# PRoMo_Base_DIP.net
KiCad netlist of a schematic drawn in EAGLE
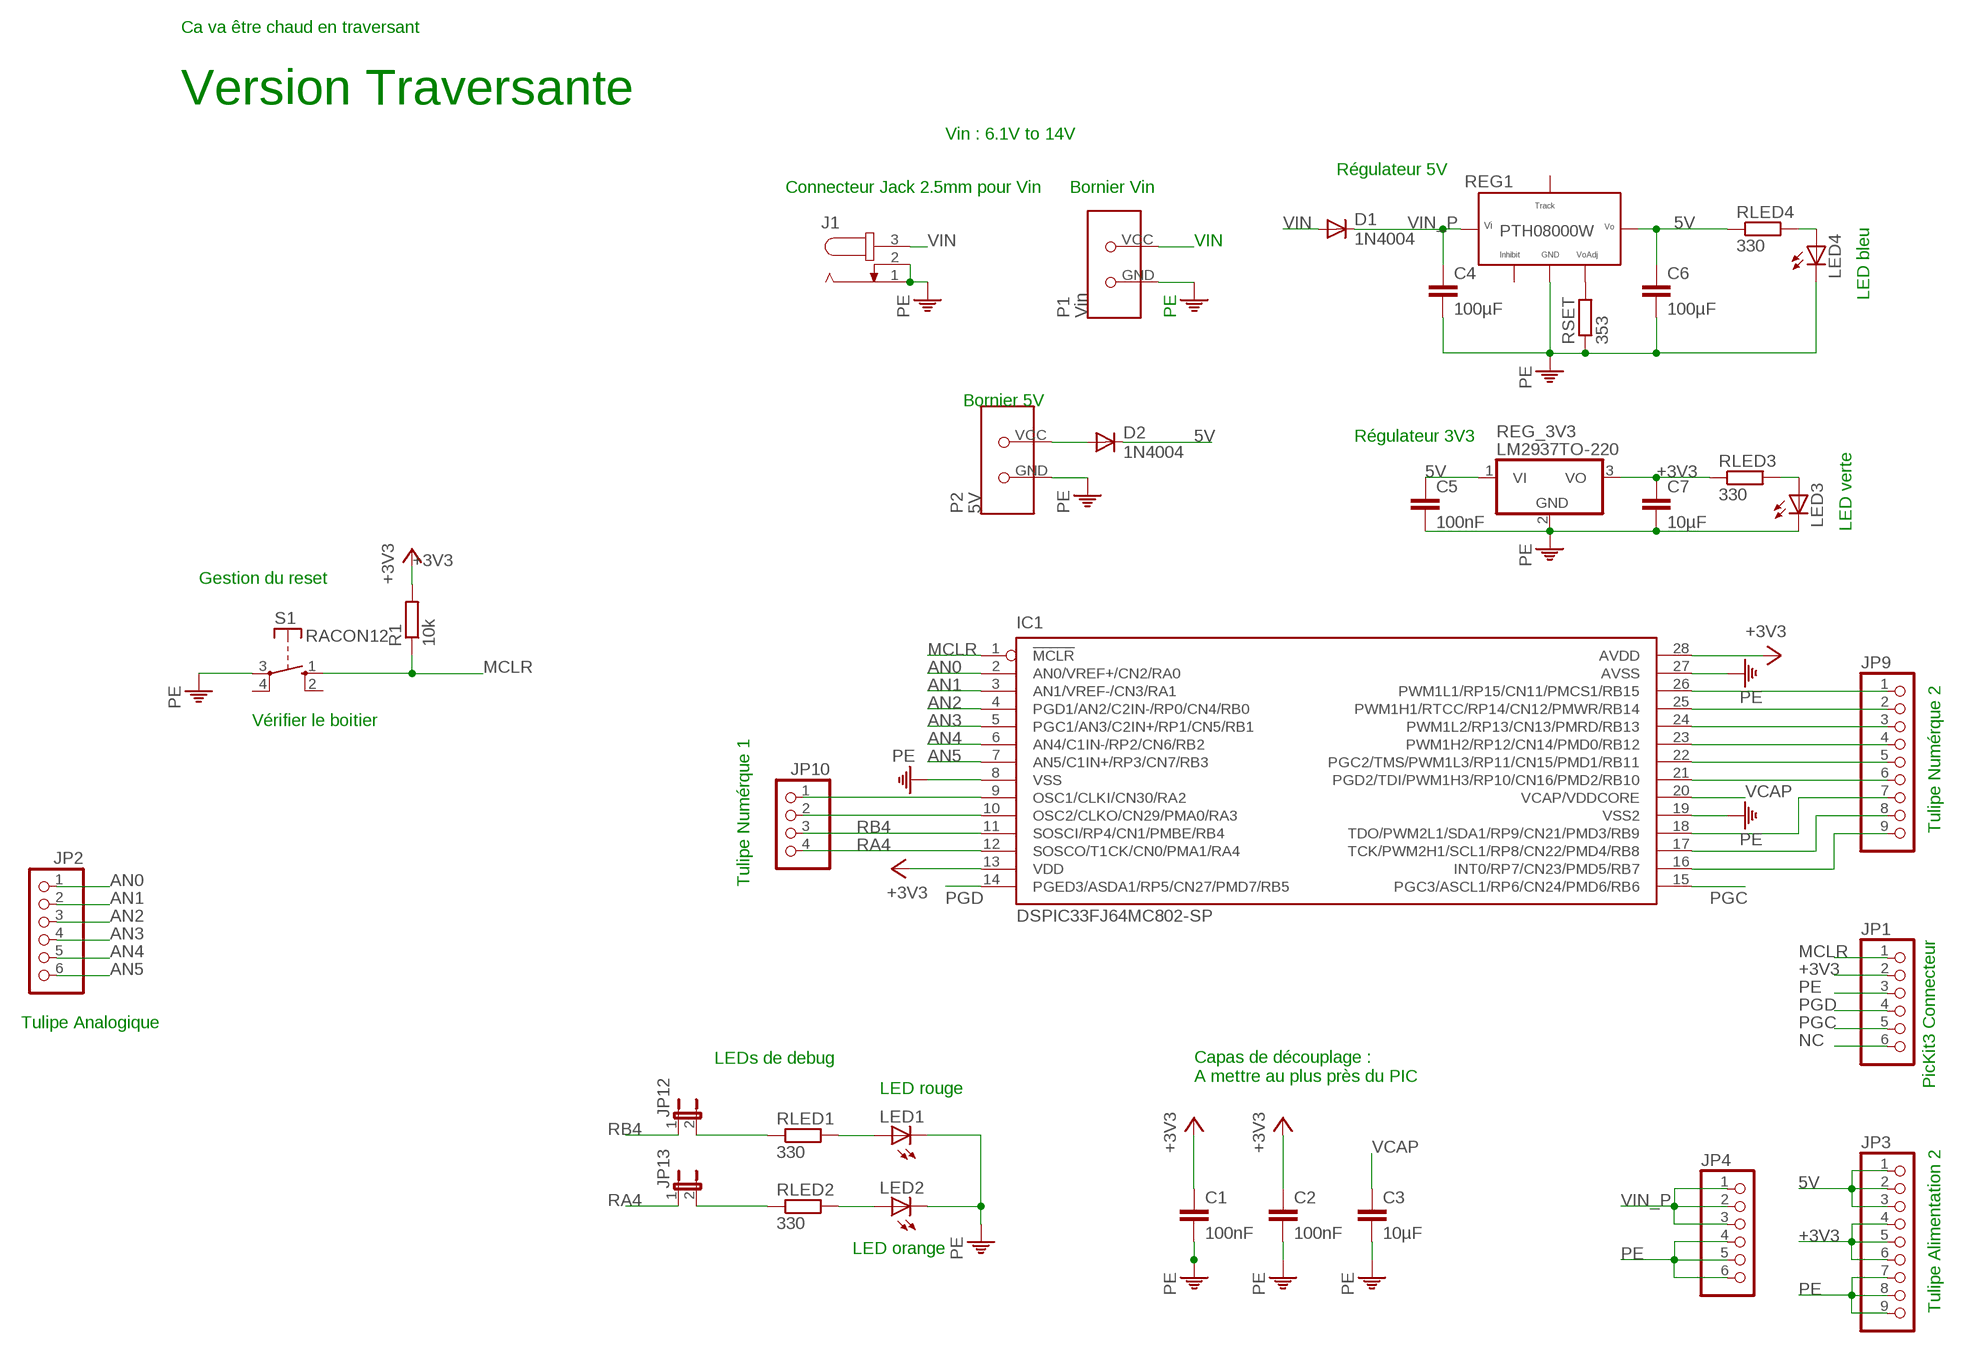
[diagram p0: schematic, sheet 1]

(export (version "E")
  (design (tool "Eeschema 10.0.6"))
  (components
    (comp (ref "C1")
      (value "100nF")
      (footprint "eagle-import:C102-043X133")
      (libsource (lib "eagle-import") (part "C-EU102-043X133"))
    )
    (comp (ref "C2")
      (value "100nF")
      (footprint "eagle-import:C050-035X075")
      (libsource (lib "eagle-import") (part "C-EU050-035X075"))
    )
    (comp (ref "C3")
      (value "10µF")
      (footprint "eagle-import:C050-035X075")
      (libsource (lib "eagle-import") (part "C-EU050-035X075"))
    )
    (comp (ref "C4")
      (value "100µF")
      (footprint "eagle-import:C050-035X075")
      (libsource (lib "eagle-import") (part "C-EU050-035X075"))
    )
    (comp (ref "C5")
      (value "100nF")
      (footprint "eagle-import:C050-035X075")
      (libsource (lib "eagle-import") (part "C-EU050-035X075"))
    )
    (comp (ref "C6")
      (value "100µF")
      (footprint "eagle-import:C050-035X075")
      (libsource (lib "eagle-import") (part "C-EU050-035X075"))
    )
    (comp (ref "C7")
      (value "10µF")
      (footprint "eagle-import:C050-035X075")
      (libsource (lib "eagle-import") (part "C-EU050-035X075"))
    )
    (comp (ref "D1")
      (value "1N4004")
      (footprint "eagle-import:DO41-10")
      (libsource (lib "eagle-import") (part "1N4004"))
    )
    (comp (ref "D2")
      (value "1N4004")
      (footprint "eagle-import:DO41-10")
      (libsource (lib "eagle-import") (part "1N4004"))
    )
    (comp (ref "IC1")
      (value "DSPIC33FJ64MC802-SP")
      (footprint "eagle-import:DIL28-3")
      (libsource (lib "eagle-import") (part "DSPIC33FJ64MC802-SP"))
    )
    (comp (ref "J1")
      (value "JACK-PLUG1")
      (footprint "eagle-import:SPC4078")
      (libsource (lib "eagle-import") (part "JACK-PLUG1"))
    )
    (comp (ref "JP1")
      (value "PINHD-1X6/90")
      (footprint "eagle-import:1X06_90")
      (libsource (lib "eagle-import") (part "PINHD-1X6/90"))
    )
    (comp (ref "JP2")
      (value "PINHD-1X6")
      (footprint "eagle-import:1X06")
      (libsource (lib "eagle-import") (part "PINHD-1X6"))
    )
    (comp (ref "JP3")
      (value "PINHD-1X9")
      (footprint "eagle-import:1X09")
      (libsource (lib "eagle-import") (part "PINHD-1X9"))
    )
    (comp (ref "JP4")
      (value "PINHD-1X6")
      (footprint "eagle-import:1X06")
      (libsource (lib "eagle-import") (part "PINHD-1X6"))
    )
    (comp (ref "JP9")
      (value "PINHD-1X9")
      (footprint "eagle-import:1X09")
      (libsource (lib "eagle-import") (part "PINHD-1X9"))
    )
    (comp (ref "JP10")
      (value "PINHD-1X4")
      (footprint "eagle-import:1X04")
      (libsource (lib "eagle-import") (part "PINHD-1X4"))
    )
    (comp (ref "JP12")
      (value "JP1E")
      (footprint "eagle-import:JP1")
      (libsource (lib "eagle-import") (part "JP1E"))
    )
    (comp (ref "JP13")
      (value "JP1E")
      (footprint "eagle-import:JP1")
      (libsource (lib "eagle-import") (part "JP1E"))
    )
    (comp (ref "LED1")
      (value "LED3MM")
      (footprint "eagle-import:LED3MM")
      (libsource (lib "eagle-import") (part "LED3MM"))
    )
    (comp (ref "LED2")
      (value "LED3MM")
      (footprint "eagle-import:LED3MM")
      (libsource (lib "eagle-import") (part "LED3MM"))
    )
    (comp (ref "LED3")
      (value "LED3MM")
      (footprint "eagle-import:LED3MM")
      (libsource (lib "eagle-import") (part "LED3MM"))
    )
    (comp (ref "LED4")
      (value "LED3MM")
      (footprint "eagle-import:LED3MM")
      (libsource (lib "eagle-import") (part "LED3MM"))
    )
    (comp (ref "P1")
      (value "Vin")
      (footprint "eagle-import:BORNIER_COUDEE_3.5")
      (libsource (lib "eagle-import") (part "BORNIER_3.5MM"))
    )
    (comp (ref "P2")
      (value "5V")
      (footprint "eagle-import:BORNIER_COUDEE_3.5")
      (libsource (lib "eagle-import") (part "BORNIER_3.5MM"))
    )
    (comp (ref "R1")
      (value "10k")
      (footprint "eagle-import:0204_7")
      (libsource (lib "eagle-import") (part "R-EU_0204/7"))
    )
    (comp (ref "REG1")
      (value "PTH08000W(EUS)")
      (footprint "eagle-import:TRHOUGH_HOLE_(EUS)")
      (libsource (lib "eagle-import") (part "PTH08000W(EUS)"))
    )
    (comp (ref "REG_3V3")
      (value "LM2937TO-220")
      (footprint "eagle-import:TO220V")
      (libsource (lib "eagle-import") (part "LM2937TO-220"))
    )
    (comp (ref "RLED1")
      (value "330")
      (footprint "eagle-import:0204_7")
      (libsource (lib "eagle-import") (part "R-EU_0204/7"))
    )
    (comp (ref "RLED2")
      (value "330")
      (footprint "eagle-import:0204_7")
      (libsource (lib "eagle-import") (part "R-EU_0204/7"))
    )
    (comp (ref "RLED3")
      (value "330")
      (footprint "eagle-import:0204_7")
      (libsource (lib "eagle-import") (part "R-EU_0204/7"))
    )
    (comp (ref "RLED4")
      (value "330")
      (footprint "eagle-import:0204_7")
      (libsource (lib "eagle-import") (part "R-EU_0204/7"))
    )
    (comp (ref "RSET")
      (value "353")
      (footprint "eagle-import:0204_7")
      (libsource (lib "eagle-import") (part "R-EU_0204/7"))
    )
    (comp (ref "S1")
      (value "RACON12")
      (footprint "eagle-import:RACON12")
      (libsource (lib "eagle-import") (part "RACON12"))
    )
  )
  (nets
    (net (code "1") (name "+3V3") (class "Default")
      (node (ref "C1") (pin "1") (pinfunction "1_1") (pintype "passive"))
      (node (ref "C2") (pin "1") (pinfunction "1_1") (pintype "passive"))
      (node (ref "C7") (pin "1") (pinfunction "1_1") (pintype "passive"))
      (node (ref "IC1") (pin "13") (pinfunction "VDD_13") (pintype "power_in"))
      (node (ref "IC1") (pin "28") (pinfunction "AVDD_28") (pintype "power_in"))
      (node (ref "JP1") (pin "2") (pinfunction "2_2") (pintype "passive"))
      (node (ref "JP3") (pin "4") (pinfunction "4_4") (pintype "passive"))
      (node (ref "JP3") (pin "5") (pinfunction "5_5") (pintype "passive"))
      (node (ref "JP3") (pin "6") (pinfunction "6_6") (pintype "passive"))
      (node (ref "R1") (pin "2") (pinfunction "2_2") (pintype "passive"))
      (node (ref "REG_3V3") (pin "3") (pinfunction "VO_3") (pintype "passive"))
      (node (ref "RLED3") (pin "1") (pinfunction "1_1") (pintype "passive"))
    )
    (net (code "2") (name "/5V") (class "Default")
      (node (ref "C5") (pin "1") (pinfunction "1_1") (pintype "passive"))
      (node (ref "C6") (pin "1") (pinfunction "1_1") (pintype "passive"))
      (node (ref "D2") (pin "C") (pinfunction "C_C") (pintype "passive"))
      (node (ref "JP3") (pin "1") (pinfunction "1_1") (pintype "passive"))
      (node (ref "JP3") (pin "2") (pinfunction "2_2") (pintype "passive"))
      (node (ref "JP3") (pin "3") (pinfunction "3_3") (pintype "passive"))
      (node (ref "REG1") (pin "6") (pinfunction "6_6") (pintype "bidirectional"))
      (node (ref "REG_3V3") (pin "1") (pinfunction "VI_1") (pintype "input"))
      (node (ref "RLED4") (pin "1") (pinfunction "1_1") (pintype "passive"))
    )
    (net (code "3") (name "/AN0") (class "Default")
      (node (ref "IC1") (pin "2") (pinfunction "AN0/VREF+/CN2/RA0_2") (pintype "bidirectional"))
      (node (ref "JP2") (pin "1") (pinfunction "1_1") (pintype "passive"))
    )
    (net (code "4") (name "/AN1") (class "Default")
      (node (ref "IC1") (pin "3") (pinfunction "AN1/VREF-/CN3/RA1_3") (pintype "bidirectional"))
      (node (ref "JP2") (pin "2") (pinfunction "2_2") (pintype "passive"))
    )
    (net (code "5") (name "/AN2") (class "Default")
      (node (ref "IC1") (pin "4") (pinfunction "PGD1/AN2/C2IN-/RP0/CN4/RB0_4") (pintype "bidirectional"))
      (node (ref "JP2") (pin "3") (pinfunction "3_3") (pintype "passive"))
    )
    (net (code "6") (name "/AN3") (class "Default")
      (node (ref "IC1") (pin "5") (pinfunction "PGC1/AN3/C2IN+/RP1/CN5/RB1_5") (pintype "bidirectional"))
      (node (ref "JP2") (pin "4") (pinfunction "4_4") (pintype "passive"))
    )
    (net (code "7") (name "/AN4") (class "Default")
      (node (ref "IC1") (pin "6") (pinfunction "AN4/C1IN-/RP2/CN6/RB2_6") (pintype "bidirectional"))
      (node (ref "JP2") (pin "5") (pinfunction "5_5") (pintype "passive"))
    )
    (net (code "8") (name "/AN5") (class "Default")
      (node (ref "IC1") (pin "7") (pinfunction "AN5/C1IN+/RP3/CN7/RB3_7") (pintype "bidirectional"))
      (node (ref "JP2") (pin "6") (pinfunction "6_6") (pintype "passive"))
    )
    (net (code "9") (name "/MCLR") (class "Default")
      (node (ref "IC1") (pin "1") (pinfunction "~{MCLR}_1") (pintype "input"))
      (node (ref "JP1") (pin "1") (pinfunction "1_1") (pintype "passive"))
      (node (ref "R1") (pin "1") (pinfunction "1_1") (pintype "passive"))
      (node (ref "S1") (pin "1") (pinfunction "S_1") (pintype "passive"))
    )
    (net (code "10") (name "/NC") (class "Default")
      (node (ref "JP1") (pin "6") (pinfunction "6_6") (pintype "passive"))
    )
    (net (code "11") (name "/PGC") (class "Default")
      (node (ref "IC1") (pin "15") (pinfunction "PGC3/ASCL1/RP6/CN24/PMD6/RB6_15") (pintype "bidirectional"))
      (node (ref "JP1") (pin "5") (pinfunction "5_5") (pintype "passive"))
    )
    (net (code "12") (name "/PGD") (class "Default")
      (node (ref "IC1") (pin "14") (pinfunction "PGED3/ASDA1/RP5/CN27/PMD7/RB5_14") (pintype "bidirectional"))
      (node (ref "JP1") (pin "4") (pinfunction "4_4") (pintype "passive"))
    )
    (net (code "13") (name "/RA4") (class "Default")
      (node (ref "IC1") (pin "12") (pinfunction "SOSCO/T1CK/CN0/PMA1/RA4_12") (pintype "bidirectional"))
      (node (ref "JP10") (pin "4") (pinfunction "4_4") (pintype "passive"))
      (node (ref "JP13") (pin "1") (pinfunction "1_1") (pintype "passive"))
    )
    (net (code "14") (name "/RB4") (class "Default")
      (node (ref "IC1") (pin "11") (pinfunction "SOSCI/RP4/CN1/PMBE/RB4_11") (pintype "bidirectional"))
      (node (ref "JP10") (pin "3") (pinfunction "3_3") (pintype "passive"))
      (node (ref "JP12") (pin "1") (pinfunction "1_1") (pintype "passive"))
    )
    (net (code "15") (name "/VCAP") (class "Default")
      (node (ref "C3") (pin "1") (pinfunction "1_1") (pintype "passive"))
      (node (ref "IC1") (pin "20") (pinfunction "VCAP/VDDCORE_20") (pintype "power_in"))
    )
    (net (code "16") (name "/VIN") (class "Default")
      (node (ref "D1") (pin "A") (pinfunction "A_A") (pintype "passive"))
      (node (ref "J1") (pin "3") (pinfunction "3_3") (pintype "passive"))
      (node (ref "P1") (pin "VCC") (pinfunction "VCC_VCC") (pintype "bidirectional"))
    )
    (net (code "17") (name "/VIN_P") (class "Default")
      (node (ref "C4") (pin "1") (pinfunction "1_1") (pintype "passive"))
      (node (ref "D1") (pin "C") (pinfunction "C_C") (pintype "passive"))
      (node (ref "JP4") (pin "1") (pinfunction "1_1") (pintype "passive"))
      (node (ref "JP4") (pin "2") (pinfunction "2_2") (pintype "passive"))
      (node (ref "JP4") (pin "3") (pinfunction "3_3") (pintype "passive"))
      (node (ref "REG1") (pin "3") (pinfunction "3_3") (pintype "bidirectional"))
    )
    (net (code "18") (name "Net-(D2-PadA)") (class "Default")
      (node (ref "D2") (pin "A") (pinfunction "A_A") (pintype "passive"))
      (node (ref "P2") (pin "VCC") (pinfunction "VCC_VCC") (pintype "bidirectional"))
    )
    (net (code "19") (name "Net-(IC1-INT0{slash}RP7{slash}CN23{slash}PMD5{slash}RB7)") (class "Default")
      (node (ref "IC1") (pin "16") (pinfunction "INT0/RP7/CN23/PMD5/RB7_16") (pintype "bidirectional"))
      (node (ref "JP9") (pin "9") (pinfunction "9_9") (pintype "passive"))
    )
    (net (code "20") (name "Net-(IC1-OSC1{slash}CLKI{slash}CN30{slash}RA2)") (class "Default")
      (node (ref "IC1") (pin "9") (pinfunction "OSC1/CLKI/CN30/RA2_9") (pintype "bidirectional"))
      (node (ref "JP10") (pin "1") (pinfunction "1_1") (pintype "passive"))
    )
    (net (code "21") (name "Net-(IC1-OSC2{slash}CLKO{slash}CN29{slash}PMA0{slash}RA3)") (class "Default")
      (node (ref "IC1") (pin "10") (pinfunction "OSC2/CLKO/CN29/PMA0/RA3_10") (pintype "bidirectional"))
      (node (ref "JP10") (pin "2") (pinfunction "2_2") (pintype "passive"))
    )
    (net (code "22") (name "Net-(IC1-PGC2{slash}TMS{slash}PWM1L3{slash}RP11{slash}CN15{slash}PMD1{slash}RB11)") (class "Default")
      (node (ref "IC1") (pin "22") (pinfunction "PGC2/TMS/PWM1L3/RP11/CN15/PMD1/RB11_22") (pintype "bidirectional"))
      (node (ref "JP9") (pin "5") (pinfunction "5_5") (pintype "passive"))
    )
    (net (code "23") (name "Net-(IC1-PGD2{slash}TDI{slash}PWM1H3{slash}RP10{slash}CN16{slash}PMD2{slash}RB10)") (class "Default")
      (node (ref "IC1") (pin "21") (pinfunction "PGD2/TDI/PWM1H3/RP10/CN16/PMD2/RB10_21") (pintype "bidirectional"))
      (node (ref "JP9") (pin "6") (pinfunction "6_6") (pintype "passive"))
    )
    (net (code "24") (name "Net-(IC1-PWM1H1{slash}RTCC{slash}RP14{slash}CN12{slash}PMWR{slash}RB14)") (class "Default")
      (node (ref "IC1") (pin "25") (pinfunction "PWM1H1/RTCC/RP14/CN12/PMWR/RB14_25") (pintype "bidirectional"))
      (node (ref "JP9") (pin "2") (pinfunction "2_2") (pintype "passive"))
    )
    (net (code "25") (name "Net-(IC1-PWM1H2{slash}RP12{slash}CN14{slash}PMD0{slash}RB12)") (class "Default")
      (node (ref "IC1") (pin "23") (pinfunction "PWM1H2/RP12/CN14/PMD0/RB12_23") (pintype "bidirectional"))
      (node (ref "JP9") (pin "4") (pinfunction "4_4") (pintype "passive"))
    )
    (net (code "26") (name "Net-(IC1-PWM1L1{slash}RP15{slash}CN11{slash}PMCS1{slash}RB15)") (class "Default")
      (node (ref "IC1") (pin "26") (pinfunction "PWM1L1/RP15/CN11/PMCS1/RB15_26") (pintype "bidirectional"))
      (node (ref "JP9") (pin "1") (pinfunction "1_1") (pintype "passive"))
    )
    (net (code "27") (name "Net-(IC1-PWM1L2{slash}RP13{slash}CN13{slash}PMRD{slash}RB13)") (class "Default")
      (node (ref "IC1") (pin "24") (pinfunction "PWM1L2/RP13/CN13/PMRD/RB13_24") (pintype "bidirectional"))
      (node (ref "JP9") (pin "3") (pinfunction "3_3") (pintype "passive"))
    )
    (net (code "28") (name "Net-(IC1-TCK{slash}PWM2H1{slash}SCL1{slash}RP8{slash}CN22{slash}PMD4{slash}RB8)") (class "Default")
      (node (ref "IC1") (pin "17") (pinfunction "TCK/PWM2H1/SCL1/RP8/CN22/PMD4/RB8_17") (pintype "bidirectional"))
      (node (ref "JP9") (pin "8") (pinfunction "8_8") (pintype "passive"))
    )
    (net (code "29") (name "Net-(IC1-TDO{slash}PWM2L1{slash}SDA1{slash}RP9{slash}CN21{slash}PMD3{slash}RB9)") (class "Default")
      (node (ref "IC1") (pin "18") (pinfunction "TDO/PWM2L1/SDA1/RP9/CN21/PMD3/RB9_18") (pintype "bidirectional"))
      (node (ref "JP9") (pin "7") (pinfunction "7_7") (pintype "passive"))
    )
    (net (code "30") (name "Net-(JP12-Pad2)") (class "Default")
      (node (ref "JP12") (pin "2") (pinfunction "2_2") (pintype "passive"))
      (node (ref "RLED1") (pin "1") (pinfunction "1_1") (pintype "passive"))
    )
    (net (code "31") (name "Net-(JP13-Pad2)") (class "Default")
      (node (ref "JP13") (pin "2") (pinfunction "2_2") (pintype "passive"))
      (node (ref "RLED2") (pin "1") (pinfunction "1_1") (pintype "passive"))
    )
    (net (code "32") (name "Net-(LED1-PadA)") (class "Default")
      (node (ref "LED1") (pin "A") (pinfunction "A_A") (pintype "passive"))
      (node (ref "RLED1") (pin "2") (pinfunction "2_2") (pintype "passive"))
    )
    (net (code "33") (name "Net-(LED2-PadA)") (class "Default")
      (node (ref "LED2") (pin "A") (pinfunction "A_A") (pintype "passive"))
      (node (ref "RLED2") (pin "2") (pinfunction "2_2") (pintype "passive"))
    )
    (net (code "34") (name "Net-(LED3-PadA)") (class "Default")
      (node (ref "LED3") (pin "A") (pinfunction "A_A") (pintype "passive"))
      (node (ref "RLED3") (pin "2") (pinfunction "2_2") (pintype "passive"))
    )
    (net (code "35") (name "Net-(LED4-PadA)") (class "Default")
      (node (ref "LED4") (pin "A") (pinfunction "A_A") (pintype "passive"))
      (node (ref "RLED4") (pin "2") (pinfunction "2_2") (pintype "passive"))
    )
    (net (code "36") (name "Net-(REG1-Pad5)") (class "Default")
      (node (ref "REG1") (pin "5") (pinfunction "5_5") (pintype "bidirectional"))
      (node (ref "RSET") (pin "2") (pinfunction "2_2") (pintype "passive"))
    )
    (net (code "37") (name "PE") (class "Default")
      (node (ref "C1") (pin "2") (pinfunction "2_2") (pintype "passive"))
      (node (ref "C2") (pin "2") (pinfunction "2_2") (pintype "passive"))
      (node (ref "C3") (pin "2") (pinfunction "2_2") (pintype "passive"))
      (node (ref "C4") (pin "2") (pinfunction "2_2") (pintype "passive"))
      (node (ref "C5") (pin "2") (pinfunction "2_2") (pintype "passive"))
      (node (ref "C6") (pin "2") (pinfunction "2_2") (pintype "passive"))
      (node (ref "C7") (pin "2") (pinfunction "2_2") (pintype "passive"))
      (node (ref "IC1") (pin "19") (pinfunction "VSS2_19") (pintype "power_in"))
      (node (ref "IC1") (pin "27") (pinfunction "AVSS_27") (pintype "power_in"))
      (node (ref "IC1") (pin "8") (pinfunction "VSS_8") (pintype "power_in"))
      (node (ref "J1") (pin "1") (pinfunction "1_1") (pintype "passive"))
      (node (ref "J1") (pin "2") (pinfunction "2_2") (pintype "passive"))
      (node (ref "JP1") (pin "3") (pinfunction "3_3") (pintype "passive"))
      (node (ref "JP3") (pin "7") (pinfunction "7_7") (pintype "passive"))
      (node (ref "JP3") (pin "8") (pinfunction "8_8") (pintype "passive"))
      (node (ref "JP3") (pin "9") (pinfunction "9_9") (pintype "passive"))
      (node (ref "JP4") (pin "4") (pinfunction "4_4") (pintype "passive"))
      (node (ref "JP4") (pin "5") (pinfunction "5_5") (pintype "passive"))
      (node (ref "JP4") (pin "6") (pinfunction "6_6") (pintype "passive"))
      (node (ref "LED1") (pin "K") (pinfunction "C_K") (pintype "passive"))
      (node (ref "LED2") (pin "K") (pinfunction "C_K") (pintype "passive"))
      (node (ref "LED3") (pin "K") (pinfunction "C_K") (pintype "passive"))
      (node (ref "LED4") (pin "K") (pinfunction "C_K") (pintype "passive"))
      (node (ref "P1") (pin "GND") (pinfunction "GND_GND") (pintype "bidirectional"))
      (node (ref "P2") (pin "GND") (pinfunction "GND_GND") (pintype "bidirectional"))
      (node (ref "REG1") (pin "1") (pinfunction "1_1") (pintype "bidirectional"))
      (node (ref "REG_3V3") (pin "2") (pinfunction "GND_2") (pintype "passive"))
      (node (ref "RSET") (pin "1") (pinfunction "1_1") (pintype "passive"))
      (node (ref "S1") (pin "3") (pinfunction "P_3") (pintype "passive"))
    )
    (net (code "38") (name "unconnected-(REG1-Pad2)") (class "Default")
      (node (ref "REG1") (pin "2") (pinfunction "2_2") (pintype "bidirectional"))
    )
    (net (code "39") (name "unconnected-(REG1-Pad4)") (class "Default")
      (node (ref "REG1") (pin "4") (pinfunction "4_4") (pintype "bidirectional"))
    )
    (net (code "40") (name "unconnected-(S1-P-Pad4)") (class "Default")
      (node (ref "S1") (pin "4") (pinfunction "P_4") (pintype "passive"))
    )
    (net (code "41") (name "unconnected-(S1-S-Pad2)") (class "Default")
      (node (ref "S1") (pin "2") (pinfunction "S_2") (pintype "passive"))
    )
  )
)
